# design.net
KiCad netlist of a schematic drawn in Altium Designer
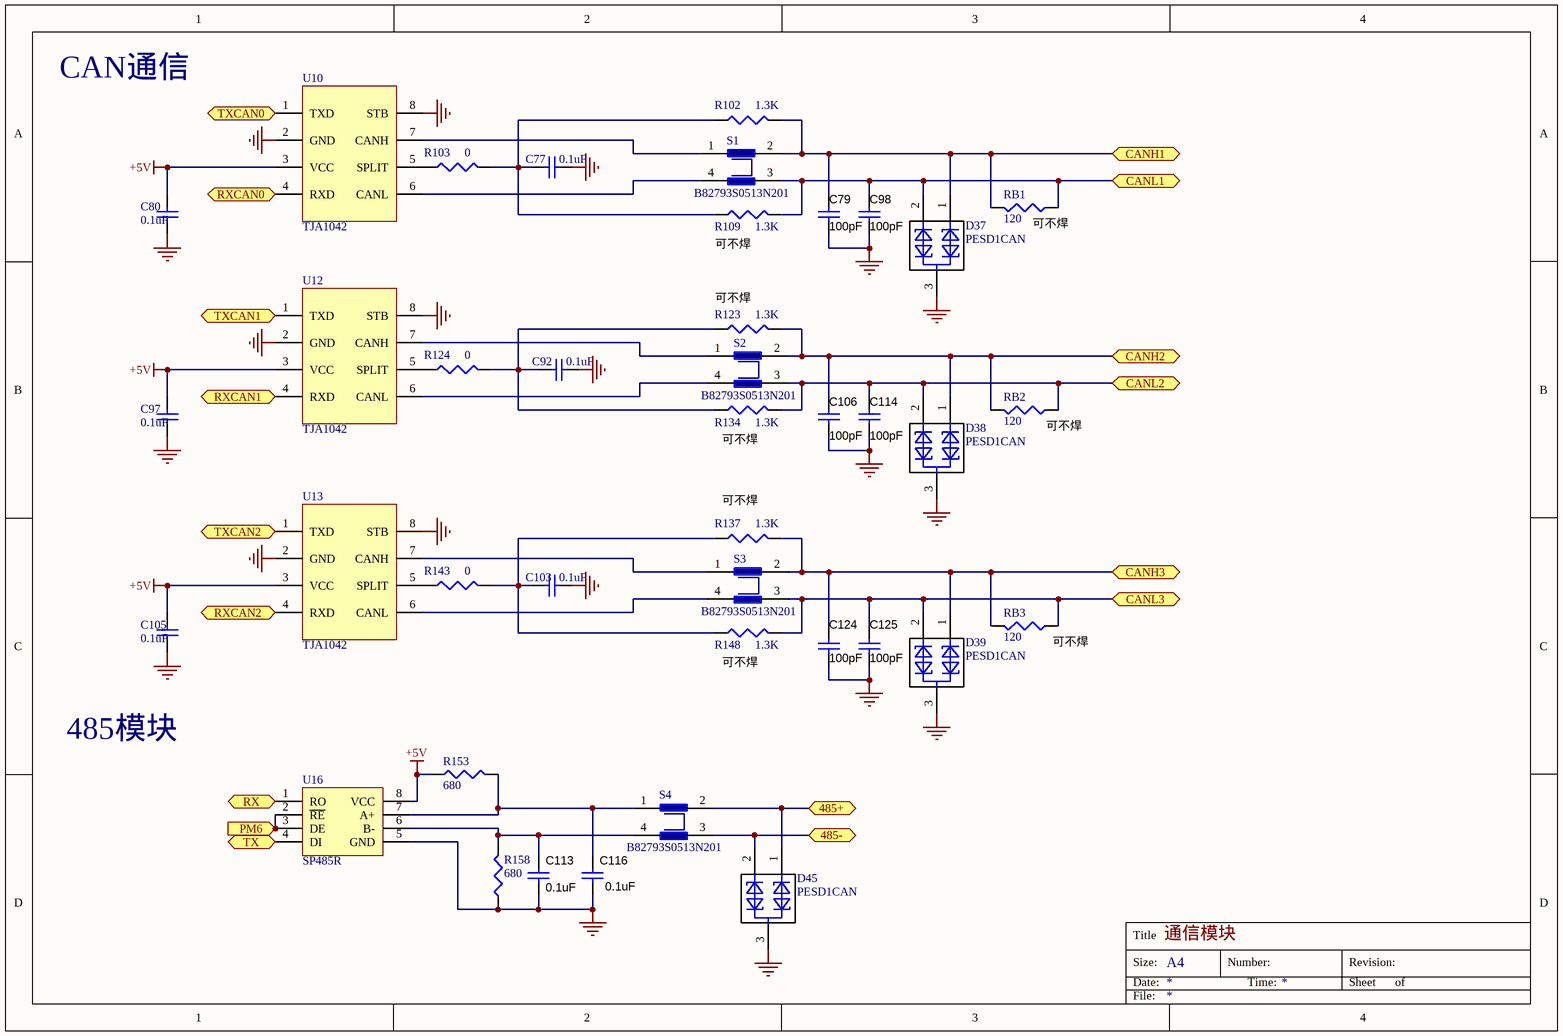
[diagram p0: 通信模块.SchDoc]

(export (version "E")
  (design (tool "Eeschema 10.0.6"))
  (components
    (comp (ref "C77")
      (value "0.1uF")
      (footprint "0603-L")
      (description "Ceramic, X7R, 100V, 10%, 0603")
      (fields (field (name "Comment") "Cap") (field (name "PUBLISHER") "Altium Limited"))
      (libsource (lib "Resistor") (part "CC0603KRX7R0BB104"))
    )
    (comp (ref "C79")
      (value "100pF")
      (footprint "0603-L")
      (description "Ceramic, X7R, 50V, 5%, 0603")
      (fields
        (field (name "MANUFACTURER") "YAGEO")
        (field (name "PARTNUMBER") "CC0603JRNPO9BN101")
        (field (name "PUBLISHER") "National Semiconductor")
      )
      (libsource (lib "Resistor") (part "CC0603JRNPO9BN101"))
    )
    (comp (ref "C80")
      (value "0.1uF")
      (footprint "0603-L")
      (description "Ceramic, X7R, 100V, 10%, 0603")
      (fields (field (name "Comment") "Cap") (field (name "PUBLISHER") "Altium Limited"))
      (libsource (lib "Resistor") (part "CC0603KRX7R0BB104"))
    )
    (comp (ref "C92")
      (value "0.1uF")
      (footprint "0603-L")
      (description "Ceramic, X7R, 100V, 10%, 0603")
      (fields (field (name "Comment") "Cap") (field (name "PUBLISHER") "Altium Limited"))
      (libsource (lib "Resistor") (part "CC0603KRX7R0BB104"))
    )
    (comp (ref "C97")
      (value "0.1uF")
      (footprint "0603-L")
      (description "Ceramic, X7R, 100V, 10%, 0603")
      (fields (field (name "Comment") "Cap") (field (name "PUBLISHER") "Altium Limited"))
      (libsource (lib "Resistor") (part "CC0603KRX7R0BB104"))
    )
    (comp (ref "C98")
      (value "100pF")
      (footprint "0603-L")
      (description "Ceramic, X7R, 50V, 5%, 0603")
      (fields
        (field (name "MANUFACTURER") "YAGEO")
        (field (name "PARTNUMBER") "CC0603JRNPO9BN101")
        (field (name "PUBLISHER") "National Semiconductor")
      )
      (libsource (lib "Resistor") (part "CC0603JRNPO9BN101"))
    )
    (comp (ref "C103")
      (value "0.1uF")
      (footprint "0603-L")
      (description "Ceramic, X7R, 100V, 10%, 0603")
      (fields (field (name "Comment") "Cap") (field (name "PUBLISHER") "Altium Limited"))
      (libsource (lib "Resistor") (part "CC0603KRX7R0BB104"))
    )
    (comp (ref "C105")
      (value "0.1uF")
      (footprint "0603-L")
      (description "Ceramic, X7R, 100V, 10%, 0603")
      (fields (field (name "Comment") "Cap") (field (name "PUBLISHER") "Altium Limited"))
      (libsource (lib "Resistor") (part "CC0603KRX7R0BB104"))
    )
    (comp (ref "C106")
      (value "100pF")
      (footprint "0603-L")
      (description "Ceramic, X7R, 50V, 5%, 0603")
      (fields
        (field (name "MANUFACTURER") "YAGEO")
        (field (name "PARTNUMBER") "CC0603JRNPO9BN101")
        (field (name "PUBLISHER") "National Semiconductor")
      )
      (libsource (lib "Resistor") (part "CC0603JRNPO9BN101"))
    )
    (comp (ref "C113")
      (value "0.1uF")
      (footprint "0603-CAPACITOR")
      (description "Ceramic, X7R, 50V, 10%")
      (fields
        (field (name "MANUFACTURER") "TDK")
        (field (name "PARTNUMBER") "C1608C0G1H200JT")
        (field (name "PUBLISHER") "National Semiconductor")
      )
      (libsource (lib "Resistor") (part "C1608X7R1H104KT"))
    )
    (comp (ref "C114")
      (value "100pF")
      (footprint "0603-L")
      (description "Ceramic, X7R, 50V, 5%, 0603")
      (fields
        (field (name "MANUFACTURER") "YAGEO")
        (field (name "PARTNUMBER") "CC0603JRNPO9BN101")
        (field (name "PUBLISHER") "National Semiconductor")
      )
      (libsource (lib "Resistor") (part "CC0603JRNPO9BN101"))
    )
    (comp (ref "C116")
      (value "0.1uF")
      (footprint "0603-CAPACITOR")
      (description "Ceramic, X7R, 50V, 10%")
      (fields
        (field (name "MANUFACTURER") "TDK")
        (field (name "PARTNUMBER") "C1608C0G1H200JT")
        (field (name "PUBLISHER") "National Semiconductor")
      )
      (libsource (lib "Resistor") (part "C1608X7R1H104KT"))
    )
    (comp (ref "C124")
      (value "100pF")
      (footprint "0603-L")
      (description "Ceramic, X7R, 50V, 5%, 0603")
      (fields
        (field (name "MANUFACTURER") "YAGEO")
        (field (name "PARTNUMBER") "CC0603JRNPO9BN101")
        (field (name "PUBLISHER") "National Semiconductor")
      )
      (libsource (lib "Resistor") (part "CC0603JRNPO9BN101"))
    )
    (comp (ref "C125")
      (value "100pF")
      (footprint "0603-L")
      (description "Ceramic, X7R, 50V, 5%, 0603")
      (fields
        (field (name "MANUFACTURER") "YAGEO")
        (field (name "PARTNUMBER") "CC0603JRNPO9BN101")
        (field (name "PUBLISHER") "National Semiconductor")
      )
      (libsource (lib "Resistor") (part "CC0603JRNPO9BN101"))
    )
    (comp (ref "D37")
      (value "PESD1CAN")
      (footprint "SOT23,PESD1CAN,TO-236B")
      (description "PESD1CAN,SOT23, CAN ESD")
      (libsource (lib "BMS") (part "PESD1CAN"))
    )
    (comp (ref "D38")
      (value "PESD1CAN")
      (footprint "SOT23,PESD1CAN,TO-236B")
      (description "PESD1CAN,SOT23, CAN ESD")
      (libsource (lib "BMS") (part "PESD1CAN"))
    )
    (comp (ref "D39")
      (value "PESD1CAN")
      (footprint "SOT23,PESD1CAN,TO-236B")
      (description "PESD1CAN,SOT23, CAN ESD")
      (libsource (lib "BMS") (part "PESD1CAN"))
    )
    (comp (ref "D45")
      (value "PESD1CAN")
      (footprint "SOT23,PESD1CAN,TO-236B")
      (description "PESD1CAN,SOT23, CAN ESD")
      (libsource (lib "BMS") (part "PESD1CAN"))
    )
    (comp (ref "R102")
      (value "1.3K")
      (footprint "RES0805")
      (description "Resistor")
      (fields (field (name "Comment") "Res3") (field (name "PUBLISHER") "Altium Limited"))
      (libsource (lib "Miscellaneous Devices") (part "Res3"))
    )
    (comp (ref "R103")
      (value "0")
      (footprint "0603-L")
      (description "Resistor")
      (fields (field (name "Comment") "Res3") (field (name "PUBLISHER") "Altium Limited"))
      (libsource (lib "Miscellaneous Devices") (part "Res3"))
    )
    (comp (ref "R109")
      (value "1.3K")
      (footprint "RES0805")
      (description "Resistor")
      (fields (field (name "Comment") "Res3") (field (name "PUBLISHER") "Altium Limited"))
      (libsource (lib "Miscellaneous Devices") (part "Res3"))
    )
    (comp (ref "R123")
      (value "1.3K")
      (footprint "RES0805")
      (description "Resistor")
      (fields (field (name "Comment") "Res3") (field (name "PUBLISHER") "Altium Limited"))
      (libsource (lib "Miscellaneous Devices") (part "Res3"))
    )
    (comp (ref "R124")
      (value "0")
      (footprint "0603-L")
      (description "Resistor")
      (fields (field (name "Comment") "Res3") (field (name "PUBLISHER") "Altium Limited"))
      (libsource (lib "Miscellaneous Devices") (part "Res3"))
    )
    (comp (ref "R134")
      (value "1.3K")
      (footprint "RES0805")
      (description "Resistor")
      (fields (field (name "Comment") "Res3") (field (name "PUBLISHER") "Altium Limited"))
      (libsource (lib "Miscellaneous Devices") (part "Res3"))
    )
    (comp (ref "R137")
      (value "1.3K")
      (footprint "RES0805")
      (description "Resistor")
      (fields (field (name "Comment") "Res3") (field (name "PUBLISHER") "Altium Limited"))
      (libsource (lib "Miscellaneous Devices") (part "Res3"))
    )
    (comp (ref "R143")
      (value "0")
      (footprint "0603-L")
      (description "Resistor")
      (fields (field (name "Comment") "Res3") (field (name "PUBLISHER") "Altium Limited"))
      (libsource (lib "Miscellaneous Devices") (part "Res3"))
    )
    (comp (ref "R148")
      (value "1.3K")
      (footprint "RES0805")
      (description "Resistor")
      (fields (field (name "Comment") "Res3") (field (name "PUBLISHER") "Altium Limited"))
      (libsource (lib "Miscellaneous Devices") (part "Res3"))
    )
    (comp (ref "R153")
      (value "680")
      (footprint "J1-0603")
      (description "Resistor")
      (fields (field (name "Comment") "Res3") (field (name "PUBLISHER") "Altium Limited"))
      (libsource (lib "Miscellaneous Devices") (part "Res3"))
    )
    (comp (ref "R158")
      (value "680")
      (footprint "J1-0603")
      (description "Resistor")
      (fields (field (name "Comment") "Res3") (field (name "PUBLISHER") "Altium Limited"))
      (libsource (lib "Miscellaneous Devices") (part "Res3"))
    )
    (comp (ref "RB1")
      (value "120")
      (footprint "RES1206")
      (description "Resistor")
      (fields (field (name "Comment") "Res3") (field (name "PUBLISHER") "Altium Limited"))
      (libsource (lib "Miscellaneous Devices") (part "Res3"))
    )
    (comp (ref "RB2")
      (value "120")
      (footprint "RES1206")
      (description "Resistor")
      (fields (field (name "Comment") "Res3") (field (name "PUBLISHER") "Altium Limited"))
      (libsource (lib "Miscellaneous Devices") (part "Res3"))
    )
    (comp (ref "RB3")
      (value "120")
      (footprint "RES1206")
      (description "Resistor")
      (fields (field (name "Comment") "Res3") (field (name "PUBLISHER") "Altium Limited"))
      (libsource (lib "Miscellaneous Devices") (part "Res3"))
    )
    (comp (ref "S1")
      (value "B82793S0513N201")
      (footprint "SMD")
      (description "TDK, Common-mode Choke, CAN & FlexRay")
      (libsource (lib "BMS") (part "B82793S0513N201"))
    )
    (comp (ref "S2")
      (value "B82793S0513N201")
      (footprint "SMD")
      (description "TDK, Common-mode Choke, CAN & FlexRay")
      (libsource (lib "BMS") (part "B82793S0513N201"))
    )
    (comp (ref "S3")
      (value "B82793S0513N201")
      (footprint "SMD")
      (description "TDK, Common-mode Choke, CAN & FlexRay")
      (libsource (lib "BMS") (part "B82793S0513N201"))
    )
    (comp (ref "S4")
      (value "B82793S0513N201")
      (footprint "SMD")
      (description "TDK, Common-mode Choke, CAN & FlexRay")
      (libsource (lib "BMS") (part "B82793S0513N201"))
    )
    (comp (ref "U10") (value "TJA1042") (footprint "TJA10") (libsource (lib "整车控制器") (part "TJA1042")))
    (comp (ref "U12") (value "TJA1042") (footprint "TJA10") (libsource (lib "整车控制器") (part "TJA1042")))
    (comp (ref "U13") (value "TJA1042") (footprint "TJA10") (libsource (lib "整车控制器") (part "TJA1042")))
    (comp (ref "U16") (value "SP485R") (footprint "VCU:U16") (libsource (lib "BMS") (part "SP485R")))
  )
  (nets
    (net (code "1") (name "+5V") (class "Default")
      (node (ref "C105") (pin "1") (pinfunction "1_1") (pintype "passive"))
      (node (ref "C80") (pin "1") (pinfunction "1_1") (pintype "passive"))
      (node (ref "C97") (pin "1") (pinfunction "1_1") (pintype "passive"))
      (node (ref "R153") (pin "1") (pinfunction "1_1") (pintype "passive"))
      (node (ref "U10") (pin "3") (pinfunction "VCC_3") (pintype "passive"))
      (node (ref "U12") (pin "3") (pinfunction "VCC_3") (pintype "passive"))
      (node (ref "U13") (pin "3") (pinfunction "VCC_3") (pintype "passive"))
      (node (ref "U16") (pin "8") (pinfunction "VCC_8") (pintype "passive"))
    )
    (net (code "2") (name "/485+") (class "Default")
      (node (ref "D45") (pin "1") (pinfunction "1_1") (pintype "passive"))
      (node (ref "S4") (pin "2") (pinfunction "2_2") (pintype "passive"))
    )
    (net (code "3") (name "/485-") (class "Default")
      (node (ref "D45") (pin "2") (pinfunction "2_2") (pintype "passive"))
      (node (ref "S4") (pin "3") (pinfunction "3_3") (pintype "passive"))
    )
    (net (code "4") (name "/CANH1") (class "Default")
      (node (ref "C79") (pin "2") (pinfunction "2_2") (pintype "passive"))
      (node (ref "D37") (pin "1") (pinfunction "1_1") (pintype "passive"))
      (node (ref "R102") (pin "1") (pinfunction "1_1") (pintype "passive"))
      (node (ref "RB1") (pin "2") (pinfunction "2_2") (pintype "passive"))
      (node (ref "S1") (pin "2") (pinfunction "2_2") (pintype "passive"))
    )
    (net (code "5") (name "/CANH2") (class "Default")
      (node (ref "C106") (pin "2") (pinfunction "2_2") (pintype "passive"))
      (node (ref "D38") (pin "1") (pinfunction "1_1") (pintype "passive"))
      (node (ref "R123") (pin "1") (pinfunction "1_1") (pintype "passive"))
      (node (ref "RB2") (pin "2") (pinfunction "2_2") (pintype "passive"))
      (node (ref "S2") (pin "2") (pinfunction "2_2") (pintype "passive"))
    )
    (net (code "6") (name "/CANH3") (class "Default")
      (node (ref "C124") (pin "2") (pinfunction "2_2") (pintype "passive"))
      (node (ref "D39") (pin "1") (pinfunction "1_1") (pintype "passive"))
      (node (ref "R137") (pin "1") (pinfunction "1_1") (pintype "passive"))
      (node (ref "RB3") (pin "2") (pinfunction "2_2") (pintype "passive"))
      (node (ref "S3") (pin "2") (pinfunction "2_2") (pintype "passive"))
    )
    (net (code "7") (name "/CANL1") (class "Default")
      (node (ref "C98") (pin "2") (pinfunction "2_2") (pintype "passive"))
      (node (ref "D37") (pin "2") (pinfunction "2_2") (pintype "passive"))
      (node (ref "R109") (pin "1") (pinfunction "1_1") (pintype "passive"))
      (node (ref "RB1") (pin "1") (pinfunction "1_1") (pintype "passive"))
      (node (ref "S1") (pin "3") (pinfunction "3_3") (pintype "passive"))
    )
    (net (code "8") (name "/CANL2") (class "Default")
      (node (ref "C114") (pin "2") (pinfunction "2_2") (pintype "passive"))
      (node (ref "D38") (pin "2") (pinfunction "2_2") (pintype "passive"))
      (node (ref "R134") (pin "1") (pinfunction "1_1") (pintype "passive"))
      (node (ref "RB2") (pin "1") (pinfunction "1_1") (pintype "passive"))
      (node (ref "S2") (pin "3") (pinfunction "3_3") (pintype "passive"))
    )
    (net (code "9") (name "/CANL3") (class "Default")
      (node (ref "C125") (pin "2") (pinfunction "2_2") (pintype "passive"))
      (node (ref "D39") (pin "2") (pinfunction "2_2") (pintype "passive"))
      (node (ref "R148") (pin "1") (pinfunction "1_1") (pintype "passive"))
      (node (ref "RB3") (pin "1") (pinfunction "1_1") (pintype "passive"))
      (node (ref "S3") (pin "3") (pinfunction "3_3") (pintype "passive"))
    )
    (net (code "10") (name "/PM6") (class "Default")
      (node (ref "U16") (pin "2") (pinfunction "~{RE}_2") (pintype "passive"))
      (node (ref "U16") (pin "3") (pinfunction "DE_3") (pintype "passive"))
    )
    (net (code "11") (name "/RX") (class "Default")
      (node (ref "U16") (pin "1") (pinfunction "RO_1") (pintype "passive"))
    )
    (net (code "12") (name "/RXCAN0") (class "Default")
      (node (ref "U10") (pin "4") (pinfunction "RXD_4") (pintype "passive"))
    )
    (net (code "13") (name "/RXCAN1") (class "Default")
      (node (ref "U12") (pin "4") (pinfunction "RXD_4") (pintype "passive"))
    )
    (net (code "14") (name "/RXCAN2") (class "Default")
      (node (ref "U13") (pin "4") (pinfunction "RXD_4") (pintype "passive"))
    )
    (net (code "15") (name "/TX") (class "Default")
      (node (ref "U16") (pin "4") (pinfunction "DI_4") (pintype "passive"))
    )
    (net (code "16") (name "/TXCAN0") (class "Default")
      (node (ref "U10") (pin "1") (pinfunction "TXD_1") (pintype "passive"))
    )
    (net (code "17") (name "/TXCAN1") (class "Default")
      (node (ref "U12") (pin "1") (pinfunction "TXD_1") (pintype "passive"))
    )
    (net (code "18") (name "/TXCAN2") (class "Default")
      (node (ref "U13") (pin "1") (pinfunction "TXD_1") (pintype "passive"))
    )
    (net (code "19") (name "GND") (class "Default")
      (node (ref "C103") (pin "2") (pinfunction "2_2") (pintype "passive"))
      (node (ref "C105") (pin "2") (pinfunction "2_2") (pintype "passive"))
      (node (ref "C106") (pin "1") (pinfunction "1_1") (pintype "passive"))
      (node (ref "C113") (pin "2") (pinfunction "2_2") (pintype "passive"))
      (node (ref "C114") (pin "1") (pinfunction "1_1") (pintype "passive"))
      (node (ref "C116") (pin "2") (pinfunction "2_2") (pintype "passive"))
      (node (ref "C124") (pin "1") (pinfunction "1_1") (pintype "passive"))
      (node (ref "C125") (pin "1") (pinfunction "1_1") (pintype "passive"))
      (node (ref "C77") (pin "2") (pinfunction "2_2") (pintype "passive"))
      (node (ref "C79") (pin "1") (pinfunction "1_1") (pintype "passive"))
      (node (ref "C80") (pin "2") (pinfunction "2_2") (pintype "passive"))
      (node (ref "C92") (pin "2") (pinfunction "2_2") (pintype "passive"))
      (node (ref "C97") (pin "2") (pinfunction "2_2") (pintype "passive"))
      (node (ref "C98") (pin "1") (pinfunction "1_1") (pintype "passive"))
      (node (ref "D37") (pin "3") (pinfunction "3_3") (pintype "passive"))
      (node (ref "D38") (pin "3") (pinfunction "3_3") (pintype "passive"))
      (node (ref "D39") (pin "3") (pinfunction "3_3") (pintype "passive"))
      (node (ref "D45") (pin "3") (pinfunction "3_3") (pintype "passive"))
      (node (ref "R158") (pin "1") (pinfunction "1_1") (pintype "passive"))
      (node (ref "U10") (pin "2") (pinfunction "GND_2") (pintype "passive"))
      (node (ref "U10") (pin "8") (pinfunction "STB_8") (pintype "passive"))
      (node (ref "U12") (pin "2") (pinfunction "GND_2") (pintype "passive"))
      (node (ref "U12") (pin "8") (pinfunction "STB_8") (pintype "passive"))
      (node (ref "U13") (pin "2") (pinfunction "GND_2") (pintype "passive"))
      (node (ref "U13") (pin "8") (pinfunction "STB_8") (pintype "passive"))
      (node (ref "U16") (pin "5") (pinfunction "GND_5") (pintype "passive"))
    )
    (net (code "20") (name "Net-(C77-Pad1)") (class "Default")
      (node (ref "C77") (pin "1") (pinfunction "1_1") (pintype "passive"))
      (node (ref "R102") (pin "2") (pinfunction "2_2") (pintype "passive"))
      (node (ref "R103") (pin "1") (pinfunction "1_1") (pintype "passive"))
      (node (ref "R109") (pin "2") (pinfunction "2_2") (pintype "passive"))
    )
    (net (code "21") (name "Net-(C92-Pad1)") (class "Default")
      (node (ref "C92") (pin "1") (pinfunction "1_1") (pintype "passive"))
      (node (ref "R123") (pin "2") (pinfunction "2_2") (pintype "passive"))
      (node (ref "R124") (pin "1") (pinfunction "1_1") (pintype "passive"))
      (node (ref "R134") (pin "2") (pinfunction "2_2") (pintype "passive"))
    )
    (net (code "22") (name "Net-(C103-Pad1)") (class "Default")
      (node (ref "C103") (pin "1") (pinfunction "1_1") (pintype "passive"))
      (node (ref "R137") (pin "2") (pinfunction "2_2") (pintype "passive"))
      (node (ref "R143") (pin "1") (pinfunction "1_1") (pintype "passive"))
      (node (ref "R148") (pin "2") (pinfunction "2_2") (pintype "passive"))
    )
    (net (code "23") (name "Net-(U10-CANH)") (class "Default")
      (node (ref "S1") (pin "1") (pinfunction "1_1") (pintype "passive"))
      (node (ref "U10") (pin "7") (pinfunction "CANH_7") (pintype "passive"))
    )
    (net (code "24") (name "Net-(U10-CANL)") (class "Default")
      (node (ref "S1") (pin "4") (pinfunction "4_4") (pintype "passive"))
      (node (ref "U10") (pin "6") (pinfunction "CANL_6") (pintype "passive"))
    )
    (net (code "25") (name "Net-(U10-SPLIT)") (class "Default")
      (node (ref "R103") (pin "2") (pinfunction "2_2") (pintype "passive"))
      (node (ref "U10") (pin "5") (pinfunction "SPLIT_5") (pintype "passive"))
    )
    (net (code "26") (name "Net-(U12-CANH)") (class "Default")
      (node (ref "S2") (pin "1") (pinfunction "1_1") (pintype "passive"))
      (node (ref "U12") (pin "7") (pinfunction "CANH_7") (pintype "passive"))
    )
    (net (code "27") (name "Net-(U12-CANL)") (class "Default")
      (node (ref "S2") (pin "4") (pinfunction "4_4") (pintype "passive"))
      (node (ref "U12") (pin "6") (pinfunction "CANL_6") (pintype "passive"))
    )
    (net (code "28") (name "Net-(U12-SPLIT)") (class "Default")
      (node (ref "R124") (pin "2") (pinfunction "2_2") (pintype "passive"))
      (node (ref "U12") (pin "5") (pinfunction "SPLIT_5") (pintype "passive"))
    )
    (net (code "29") (name "Net-(U13-CANH)") (class "Default")
      (node (ref "S3") (pin "1") (pinfunction "1_1") (pintype "passive"))
      (node (ref "U13") (pin "7") (pinfunction "CANH_7") (pintype "passive"))
    )
    (net (code "30") (name "Net-(U13-CANL)") (class "Default")
      (node (ref "S3") (pin "4") (pinfunction "4_4") (pintype "passive"))
      (node (ref "U13") (pin "6") (pinfunction "CANL_6") (pintype "passive"))
    )
    (net (code "31") (name "Net-(U13-SPLIT)") (class "Default")
      (node (ref "R143") (pin "2") (pinfunction "2_2") (pintype "passive"))
      (node (ref "U13") (pin "5") (pinfunction "SPLIT_5") (pintype "passive"))
    )
    (net (code "32") (name "Net-(U16-A+)") (class "Default")
      (node (ref "C116") (pin "1") (pinfunction "1_1") (pintype "passive"))
      (node (ref "R153") (pin "2") (pinfunction "2_2") (pintype "passive"))
      (node (ref "S4") (pin "1") (pinfunction "1_1") (pintype "passive"))
      (node (ref "U16") (pin "7") (pinfunction "A+_7") (pintype "passive"))
    )
    (net (code "33") (name "Net-(U16-B-)") (class "Default")
      (node (ref "C113") (pin "1") (pinfunction "1_1") (pintype "passive"))
      (node (ref "R158") (pin "2") (pinfunction "2_2") (pintype "passive"))
      (node (ref "S4") (pin "4") (pinfunction "4_4") (pintype "passive"))
      (node (ref "U16") (pin "6") (pinfunction "B-_6") (pintype "passive"))
    )
  )
)
